# XO-Stick.net
KiCad netlist of a schematic drawn in EAGLE
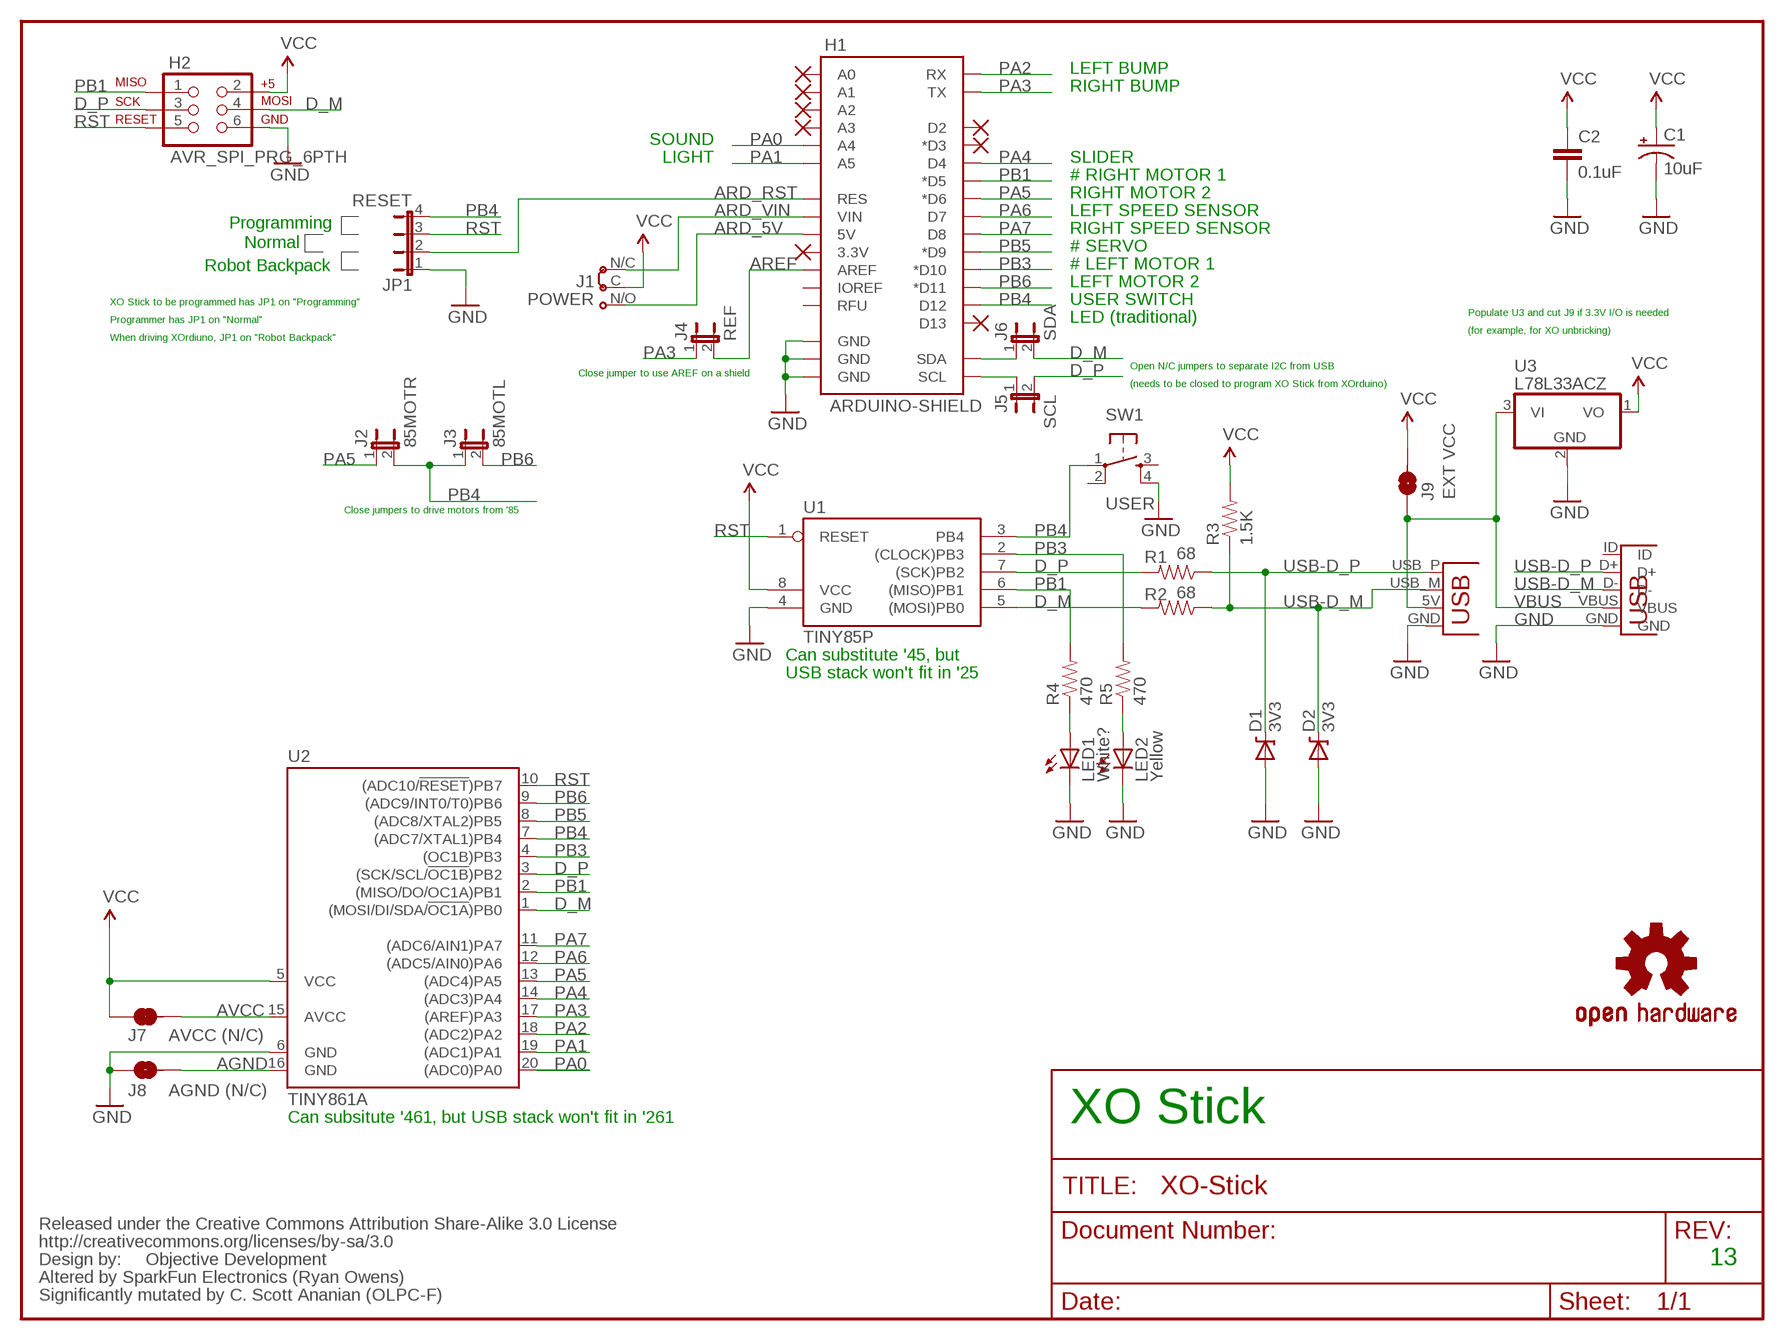
[diagram p0: schematic, sheet 1]

(export (version "E")
  (design (tool "Eeschema 10.0.6"))
  (components
    (comp (ref "C1")
      (value "10uF")
      (footprint "eagle-import:CPOL-RADIAL-10UF-25V")
      (libsource (lib "eagle-import") (part "CAP_POLPTH2"))
    )
    (comp (ref "C2")
      (value "0.1uF")
      (footprint "eagle-import:CAP-PTH-SMALL-KIT")
      (libsource (lib "eagle-import") (part "CAPKIT"))
    )
    (comp (ref "D1")
      (value "3V3")
      (footprint "eagle-import:DIODE-ZENER")
      (libsource (lib "eagle-import") (part "DIODE-ZENERPTH"))
    )
    (comp (ref "D2")
      (value "3V3")
      (footprint "eagle-import:DIODE-ZENER")
      (libsource (lib "eagle-import") (part "DIODE-ZENERPTH"))
    )
    (comp (ref "H1")
      (value "ARDUINO-SHIELD")
      (footprint "eagle-import:ARDUINO-SHIELD-VIAS-HOLES")
      (libsource (lib "eagle-import") (part "ARDUINO-SHIELD"))
    )
    (comp (ref "H2")
      (value "AVR_SPI_PRG_6PTH")
      (footprint "eagle-import:2X3")
      (libsource (lib "eagle-import") (part "AVR_SPI_PRG_6PTH"))
    )
    (comp (ref "J1")
      (value "POWER")
      (footprint "eagle-import:JP3-TRACE-NOCONFLICT")
      (libsource (lib "eagle-import") (part "JUMPER-3WAYTRACE-NOCONFLICT"))
    )
    (comp (ref "J2")
      (value "85MOTR")
      (footprint "eagle-import:SJ-2S-NO")
      (libsource (lib "eagle-import") (part "JUMPER-2SJ-NO"))
    )
    (comp (ref "J3")
      (value "85MOTL")
      (footprint "eagle-import:SJ-2S-NO")
      (libsource (lib "eagle-import") (part "JUMPER-2SJ-NO"))
    )
    (comp (ref "J4")
      (value "REF")
      (footprint "eagle-import:SJ-2S-NO")
      (libsource (lib "eagle-import") (part "JUMPER-2SJ-NO"))
    )
    (comp (ref "J5")
      (value "SCL")
      (footprint "eagle-import:SJ-2S-BOT-TRACE-NOCONFLICT-PAD")
      (libsource (lib "eagle-import") (part "JUMPER-2SJ-NC-BOT"))
    )
    (comp (ref "J6")
      (value "SDA")
      (footprint "eagle-import:SJ-2S-BOT-TRACE-NOCONFLICT-PAD")
      (libsource (lib "eagle-import") (part "JUMPER-2SJ-NC-BOT"))
    )
    (comp (ref "J7")
      (value "AVCC (N/C)")
      (footprint "eagle-import:SJ-2S-BOT-TRACE-NOCONFLICT")
      (libsource (lib "eagle-import") (part "SOLDERJUMPERBOT-NOCONFLICT"))
    )
    (comp (ref "J8")
      (value "AGND (N/C)")
      (footprint "eagle-import:SJ-2S-BOT-TRACE-NOCONFLICT")
      (libsource (lib "eagle-import") (part "SOLDERJUMPERBOT-NOCONFLICT"))
    )
    (comp (ref "J9")
      (value "EXT VCC")
      (footprint "eagle-import:SJ-2S-BOT-TRACE-NOCONFLICT-PAD")
      (libsource (lib "eagle-import") (part "SOLDERJUMPERBOT-NOCONFLICT-PAD"))
    )
    (comp (ref "JP1")
      (value "RESET")
      (footprint "eagle-import:JP4")
      (libsource (lib "eagle-import") (part "JUMPER-4"))
    )
    (comp (ref "LED1")
      (value "White?")
      (footprint "eagle-import:LED3MM-KIT")
      (libsource (lib "eagle-import") (part "LED3MM-KIT"))
    )
    (comp (ref "LED2")
      (value "Yellow")
      (footprint "eagle-import:LED3MM-KIT")
      (libsource (lib "eagle-import") (part "LED3MM-KIT"))
    )
    (comp (ref "R1")
      (value "68")
      (footprint "eagle-import:AXIAL-0.3-KIT")
      (libsource (lib "eagle-import") (part "RESISTORKIT"))
    )
    (comp (ref "R2")
      (value "68")
      (footprint "eagle-import:AXIAL-0.3-KIT")
      (libsource (lib "eagle-import") (part "RESISTORKIT"))
    )
    (comp (ref "R3")
      (value "1.5K")
      (footprint "eagle-import:AXIAL-0.3-KIT")
      (libsource (lib "eagle-import") (part "RESISTORKIT"))
    )
    (comp (ref "R4")
      (value "470")
      (footprint "eagle-import:AXIAL-0.3-KIT")
      (libsource (lib "eagle-import") (part "RESISTORKIT"))
    )
    (comp (ref "R5")
      (value "470")
      (footprint "eagle-import:AXIAL-0.3-KIT")
      (libsource (lib "eagle-import") (part "RESISTORKIT"))
    )
    (comp (ref "SW1")
      (value "USER")
      (footprint "eagle-import:TACTILE-PTH")
      (libsource (lib "eagle-import") (part "TAC_SWITCHPTH"))
    )
    (comp (ref "U$1")
      (value "OSHW-LOGOM")
      (footprint "eagle-import:OSHW-LOGO-M")
      (libsource (lib "eagle-import") (part "OSHW-LOGOM"))
    )
    (comp (ref "U$4")
      (value "CREATIVE_COMMONS")
      (footprint "eagle-import:CREATIVE_COMMONS")
      (libsource (lib "eagle-import") (part "CREATIVE_COMMONS"))
    )
    (comp (ref "U1")
      (value "TINY85P")
      (footprint "eagle-import:DIL08")
      (libsource (lib "eagle-import") (part "TINY85P"))
    )
    (comp (ref "U2")
      (value "TINY861A")
      (footprint "eagle-import:DIL20")
      (fields (field (name "MPN") "ATTINY26L-8PU"))
      (libsource (lib "eagle-import") (part "TINY26PL"))
    )
    (comp (ref "U3")
      (value "L78L33ACZ")
      (footprint "eagle-import:TO92")
      (libsource (lib "eagle-import") (part "78ZL05"))
    )
    (comp (ref "X1")
      (value "USBPCB")
      (footprint "eagle-import:USB-A-PCB")
      (libsource (lib "eagle-import") (part "USBPCB"))
    )
    (comp (ref "X2")
      (value "USBMINIB")
      (footprint "eagle-import:USB-MB-H2")
      (libsource (lib "eagle-import") (part "USBMINIB"))
    )
  )
  (nets
    (net (code "1") (name "/AGND") (class "Default")
      (node (ref "J8") (pin "2") (pinfunction "2_2") (pintype "passive"))
      (node (ref "U2") (pin "16") (pinfunction "GND_16") (pintype "power_in"))
    )
    (net (code "2") (name "/ARD_5V") (class "Default")
      (node (ref "H1") (pin "5V") (pinfunction "5V_5V") (pintype "bidirectional"))
      (node (ref "J1") (pin "N/O") (pinfunction "N/O_N/O") (pintype "passive"))
    )
    (net (code "3") (name "/ARD_RST") (class "Default")
      (node (ref "H1") (pin "RES") (pinfunction "RES_RES") (pintype "bidirectional"))
      (node (ref "JP1") (pin "2") (pinfunction "2_2") (pintype "passive"))
    )
    (net (code "4") (name "/ARD_VIN") (class "Default")
      (node (ref "H1") (pin "VIN") (pinfunction "VIN_VIN") (pintype "bidirectional"))
      (node (ref "J1") (pin "N/C") (pinfunction "N/C_N/C") (pintype "passive"))
    )
    (net (code "5") (name "/AREF") (class "Default")
      (node (ref "H1") (pin "AREF") (pinfunction "AREF_AREF") (pintype "bidirectional"))
      (node (ref "J4") (pin "2") (pinfunction "2_2") (pintype "passive"))
    )
    (net (code "6") (name "/AVCC") (class "Default")
      (node (ref "J7") (pin "2") (pinfunction "2_2") (pintype "passive"))
      (node (ref "U2") (pin "15") (pinfunction "AVCC_15") (pintype "power_in"))
    )
    (net (code "7") (name "/D_M") (class "Default")
      (node (ref "H2") (pin "4") (pinfunction "4_4") (pintype "passive"))
      (node (ref "J6") (pin "2") (pinfunction "2_2") (pintype "passive"))
      (node (ref "R2") (pin "P$2") (pinfunction "2_P$2") (pintype "passive"))
      (node (ref "U1") (pin "5") (pinfunction "(MOSI)PB0_5") (pintype "bidirectional"))
      (node (ref "U2") (pin "1") (pinfunction "(MOSI/DI/SDA/~{OC1A})PB0_1") (pintype "bidirectional"))
    )
    (net (code "8") (name "/D_P") (class "Default")
      (node (ref "H2") (pin "3") (pinfunction "3_3") (pintype "passive"))
      (node (ref "J5") (pin "2") (pinfunction "2_2") (pintype "passive"))
      (node (ref "R1") (pin "P$2") (pinfunction "2_P$2") (pintype "passive"))
      (node (ref "U1") (pin "7") (pinfunction "(SCK)PB2_7") (pintype "bidirectional"))
      (node (ref "U2") (pin "3") (pinfunction "(SCK/SCL/~{OC1B})PB2_3") (pintype "bidirectional"))
    )
    (net (code "9") (name "/PA0") (class "Default")
      (node (ref "H1") (pin "A4") (pinfunction "A4_A4") (pintype "bidirectional"))
      (node (ref "U2") (pin "20") (pinfunction "(ADC0)PA0_20") (pintype "bidirectional"))
    )
    (net (code "10") (name "/PA1") (class "Default")
      (node (ref "H1") (pin "A5") (pinfunction "A5_A5") (pintype "bidirectional"))
      (node (ref "U2") (pin "19") (pinfunction "(ADC1)PA1_19") (pintype "bidirectional"))
    )
    (net (code "11") (name "/PA2") (class "Default")
      (node (ref "H1") (pin "RX") (pinfunction "RX_RX") (pintype "bidirectional"))
      (node (ref "U2") (pin "18") (pinfunction "(ADC2)PA2_18") (pintype "bidirectional"))
    )
    (net (code "12") (name "/PA3") (class "Default")
      (node (ref "H1") (pin "TX") (pinfunction "TX_TX") (pintype "bidirectional"))
      (node (ref "J4") (pin "1") (pinfunction "1_1") (pintype "passive"))
      (node (ref "U2") (pin "17") (pinfunction "(AREF)PA3_17") (pintype "bidirectional"))
    )
    (net (code "13") (name "/PA4") (class "Default")
      (node (ref "H1") (pin "D4") (pinfunction "D4_D4") (pintype "bidirectional"))
      (node (ref "U2") (pin "14") (pinfunction "(ADC3)PA4_14") (pintype "bidirectional"))
    )
    (net (code "14") (name "/PA5") (class "Default")
      (node (ref "H1") (pin "D6") (pinfunction "*D6_D6") (pintype "bidirectional"))
      (node (ref "J2") (pin "1") (pinfunction "1_1") (pintype "passive"))
      (node (ref "U2") (pin "13") (pinfunction "(ADC4)PA5_13") (pintype "bidirectional"))
    )
    (net (code "15") (name "/PA6") (class "Default")
      (node (ref "H1") (pin "D7") (pinfunction "D7_D7") (pintype "bidirectional"))
      (node (ref "U2") (pin "12") (pinfunction "(ADC5/AIN0)PA6_12") (pintype "bidirectional"))
    )
    (net (code "16") (name "/PA7") (class "Default")
      (node (ref "H1") (pin "D8") (pinfunction "D8_D8") (pintype "bidirectional"))
      (node (ref "U2") (pin "11") (pinfunction "(ADC6/AIN1)PA7_11") (pintype "bidirectional"))
    )
    (net (code "17") (name "/PB1") (class "Default")
      (node (ref "H1") (pin "D5") (pinfunction "*D5_D5") (pintype "bidirectional"))
      (node (ref "H2") (pin "1") (pinfunction "1_1") (pintype "passive"))
      (node (ref "R4") (pin "P$2") (pinfunction "2_P$2") (pintype "passive"))
      (node (ref "U1") (pin "6") (pinfunction "(MISO)PB1_6") (pintype "bidirectional"))
      (node (ref "U2") (pin "2") (pinfunction "(MISO/DO/OC1A)PB1_2") (pintype "bidirectional"))
    )
    (net (code "18") (name "/PB3") (class "Default")
      (node (ref "H1") (pin "D10") (pinfunction "*D10_D10") (pintype "bidirectional"))
      (node (ref "R5") (pin "P$2") (pinfunction "2_P$2") (pintype "passive"))
      (node (ref "U1") (pin "2") (pinfunction "(CLOCK)PB3_2") (pintype "bidirectional"))
      (node (ref "U2") (pin "4") (pinfunction "(OC1B)PB3_4") (pintype "bidirectional"))
    )
    (net (code "19") (name "/PB4") (class "Default")
      (node (ref "H1") (pin "D12") (pinfunction "D12_D12") (pintype "bidirectional"))
      (node (ref "J2") (pin "2") (pinfunction "2_2") (pintype "passive"))
      (node (ref "J3") (pin "1") (pinfunction "1_1") (pintype "passive"))
      (node (ref "JP1") (pin "4") (pinfunction "4_4") (pintype "passive"))
      (node (ref "SW1") (pin "1") (pinfunction "1_1") (pintype "passive"))
      (node (ref "U1") (pin "3") (pinfunction "PB4_3") (pintype "bidirectional"))
      (node (ref "U2") (pin "7") (pinfunction "(ADC7/XTAL1)PB4_7") (pintype "bidirectional"))
    )
    (net (code "20") (name "/PB5") (class "Default")
      (node (ref "H1") (pin "D9") (pinfunction "*D9_D9") (pintype "bidirectional"))
      (node (ref "U2") (pin "8") (pinfunction "(ADC8/XTAL2)PB5_8") (pintype "bidirectional"))
    )
    (net (code "21") (name "/PB6") (class "Default")
      (node (ref "H1") (pin "D11") (pinfunction "*D11_D11") (pintype "bidirectional"))
      (node (ref "J3") (pin "2") (pinfunction "2_2") (pintype "passive"))
      (node (ref "U2") (pin "9") (pinfunction "(ADC9/INT0/T0)PB6_9") (pintype "bidirectional"))
    )
    (net (code "22") (name "/RST") (class "Default")
      (node (ref "H2") (pin "5") (pinfunction "5_5") (pintype "passive"))
      (node (ref "JP1") (pin "3") (pinfunction "3_3") (pintype "passive"))
      (node (ref "U1") (pin "1") (pinfunction "RESET_1") (pintype "input"))
      (node (ref "U2") (pin "10") (pinfunction "(ADC10/~{RESET})PB7_10") (pintype "bidirectional"))
    )
    (net (code "23") (name "/USB-D_M") (class "Default")
      (node (ref "D2") (pin "P$1") (pinfunction "C_P$1") (pintype "passive"))
      (node (ref "R2") (pin "P$1") (pinfunction "1_P$1") (pintype "passive"))
      (node (ref "R3") (pin "P$1") (pinfunction "1_P$1") (pintype "passive"))
      (node (ref "X1") (pin "USB_M") (pinfunction "D-_USB_M") (pintype "bidirectional"))
      (node (ref "X2") (pin "D-") (pinfunction "D-_D-") (pintype "bidirectional"))
    )
    (net (code "24") (name "/USB-D_P") (class "Default")
      (node (ref "D1") (pin "P$1") (pinfunction "C_P$1") (pintype "passive"))
      (node (ref "R1") (pin "P$1") (pinfunction "1_P$1") (pintype "passive"))
      (node (ref "X1") (pin "USB_P") (pinfunction "D+_USB_P") (pintype "bidirectional"))
      (node (ref "X2") (pin "D+") (pinfunction "D+_D+") (pintype "bidirectional"))
    )
    (net (code "25") (name "/VBUS") (class "Default")
      (node (ref "J9") (pin "1") (pinfunction "1_1") (pintype "passive"))
      (node (ref "U3") (pin "3") (pinfunction "VI_3") (pintype "input"))
      (node (ref "X1") (pin "5V") (pinfunction "VBUS_5V") (pintype "bidirectional"))
      (node (ref "X2") (pin "VBUS") (pinfunction "VBUS_VBUS") (pintype "bidirectional"))
    )
    (net (code "26") (name "GND") (class "Default")
      (node (ref "C1") (pin "2") (pinfunction "-_2") (pintype "passive"))
      (node (ref "C2") (pin "2") (pinfunction "2_2") (pintype "passive"))
      (node (ref "D1") (pin "P$2") (pinfunction "A_P$2") (pintype "passive"))
      (node (ref "D2") (pin "P$2") (pinfunction "A_P$2") (pintype "passive"))
      (node (ref "H1") (pin "GND@0") (pinfunction "GND_GND@0") (pintype "bidirectional"))
      (node (ref "H1") (pin "GND@1") (pinfunction "GND_GND@1") (pintype "bidirectional"))
      (node (ref "H1") (pin "GND@2") (pinfunction "GND_GND@2") (pintype "bidirectional"))
      (node (ref "H2") (pin "6") (pinfunction "6_6") (pintype "passive"))
      (node (ref "J8") (pin "1") (pinfunction "1_1") (pintype "passive"))
      (node (ref "JP1") (pin "1") (pinfunction "1_1") (pintype "passive"))
      (node (ref "LED1") (pin "K") (pinfunction "C_K") (pintype "passive"))
      (node (ref "LED2") (pin "K") (pinfunction "C_K") (pintype "passive"))
      (node (ref "SW1") (pin "4") (pinfunction "4_4") (pintype "passive"))
      (node (ref "U1") (pin "4") (pinfunction "GND_4") (pintype "power_in"))
      (node (ref "U2") (pin "6") (pinfunction "GND_6") (pintype "power_in"))
      (node (ref "U3") (pin "2") (pinfunction "GND_2") (pintype "passive"))
      (node (ref "X1") (pin "GND") (pinfunction "GND_GND") (pintype "bidirectional"))
      (node (ref "X2") (pin "GND") (pinfunction "GND_GND") (pintype "bidirectional"))
    )
    (net (code "27") (name "Net-(H1-PadSCL)") (class "Default")
      (node (ref "H1") (pin "SCL") (pinfunction "SCL_SCL") (pintype "bidirectional"))
      (node (ref "J5") (pin "1") (pinfunction "1_1") (pintype "passive"))
    )
    (net (code "28") (name "Net-(H1-PadSDA)") (class "Default")
      (node (ref "H1") (pin "SDA") (pinfunction "SDA_SDA") (pintype "bidirectional"))
      (node (ref "J6") (pin "1") (pinfunction "1_1") (pintype "passive"))
    )
    (net (code "29") (name "Net-(R4-1)") (class "Default")
      (node (ref "LED1") (pin "A") (pinfunction "A_A") (pintype "passive"))
      (node (ref "R4") (pin "P$1") (pinfunction "1_P$1") (pintype "passive"))
    )
    (net (code "30") (name "Net-(R5-1)") (class "Default")
      (node (ref "LED2") (pin "A") (pinfunction "A_A") (pintype "passive"))
      (node (ref "R5") (pin "P$1") (pinfunction "1_P$1") (pintype "passive"))
    )
    (net (code "31") (name "VCC") (class "Default")
      (node (ref "C1") (pin "1") (pinfunction "+_1") (pintype "passive"))
      (node (ref "C2") (pin "1") (pinfunction "1_1") (pintype "passive"))
      (node (ref "H2") (pin "2") (pinfunction "2_2") (pintype "passive"))
      (node (ref "J1") (pin "C") (pinfunction "C_C") (pintype "passive"))
      (node (ref "J7") (pin "1") (pinfunction "1_1") (pintype "passive"))
      (node (ref "J9") (pin "2") (pinfunction "2_2") (pintype "passive"))
      (node (ref "R3") (pin "P$2") (pinfunction "2_P$2") (pintype "passive"))
      (node (ref "U1") (pin "8") (pinfunction "VCC_8") (pintype "power_in"))
      (node (ref "U2") (pin "5") (pinfunction "VCC_5") (pintype "power_in"))
      (node (ref "U3") (pin "1") (pinfunction "VO_1") (pintype "passive"))
    )
    (net (code "32") (name "unconnected-(H1-*D3-PadD3)") (class "Default")
      (node (ref "H1") (pin "D3") (pinfunction "*D3_D3") (pintype "bidirectional"))
    )
    (net (code "33") (name "unconnected-(H1-Pad3.3V)") (class "Default")
      (node (ref "H1") (pin "3.3V") (pinfunction "3.3V_3.3V") (pintype "bidirectional"))
    )
    (net (code "34") (name "unconnected-(H1-PadA0)") (class "Default")
      (node (ref "H1") (pin "A0") (pinfunction "A0_A0") (pintype "bidirectional"))
    )
    (net (code "35") (name "unconnected-(H1-PadA1)") (class "Default")
      (node (ref "H1") (pin "A1") (pinfunction "A1_A1") (pintype "bidirectional"))
    )
    (net (code "36") (name "unconnected-(H1-PadA2)") (class "Default")
      (node (ref "H1") (pin "A2") (pinfunction "A2_A2") (pintype "bidirectional"))
    )
    (net (code "37") (name "unconnected-(H1-PadA3)") (class "Default")
      (node (ref "H1") (pin "A3") (pinfunction "A3_A3") (pintype "bidirectional"))
    )
    (net (code "38") (name "unconnected-(H1-PadD2)") (class "Default")
      (node (ref "H1") (pin "D2") (pinfunction "D2_D2") (pintype "bidirectional"))
    )
    (net (code "39") (name "unconnected-(H1-PadD13)") (class "Default")
      (node (ref "H1") (pin "D13") (pinfunction "D13_D13") (pintype "bidirectional"))
    )
    (net (code "40") (name "unconnected-(H1-PadIOREF)") (class "Default")
      (node (ref "H1") (pin "IOREF") (pinfunction "IOREF_IOREF") (pintype "bidirectional"))
    )
    (net (code "41") (name "unconnected-(H1-PadRFU)") (class "Default")
      (node (ref "H1") (pin "RFU") (pinfunction "RFU_RFU") (pintype "bidirectional"))
    )
    (net (code "42") (name "unconnected-(SW1-Pad2)") (class "Default")
      (node (ref "SW1") (pin "2") (pinfunction "2_2") (pintype "passive"))
    )
    (net (code "43") (name "unconnected-(SW1-Pad3)") (class "Default")
      (node (ref "SW1") (pin "3") (pinfunction "3_3") (pintype "passive"))
    )
    (net (code "44") (name "unconnected-(X2-PadID)") (class "Default")
      (node (ref "X2") (pin "ID") (pinfunction "ID_ID") (pintype "bidirectional"))
    )
  )
)
